# KillSwitch.net
KiCad netlist of a schematic drawn in Altium Designer
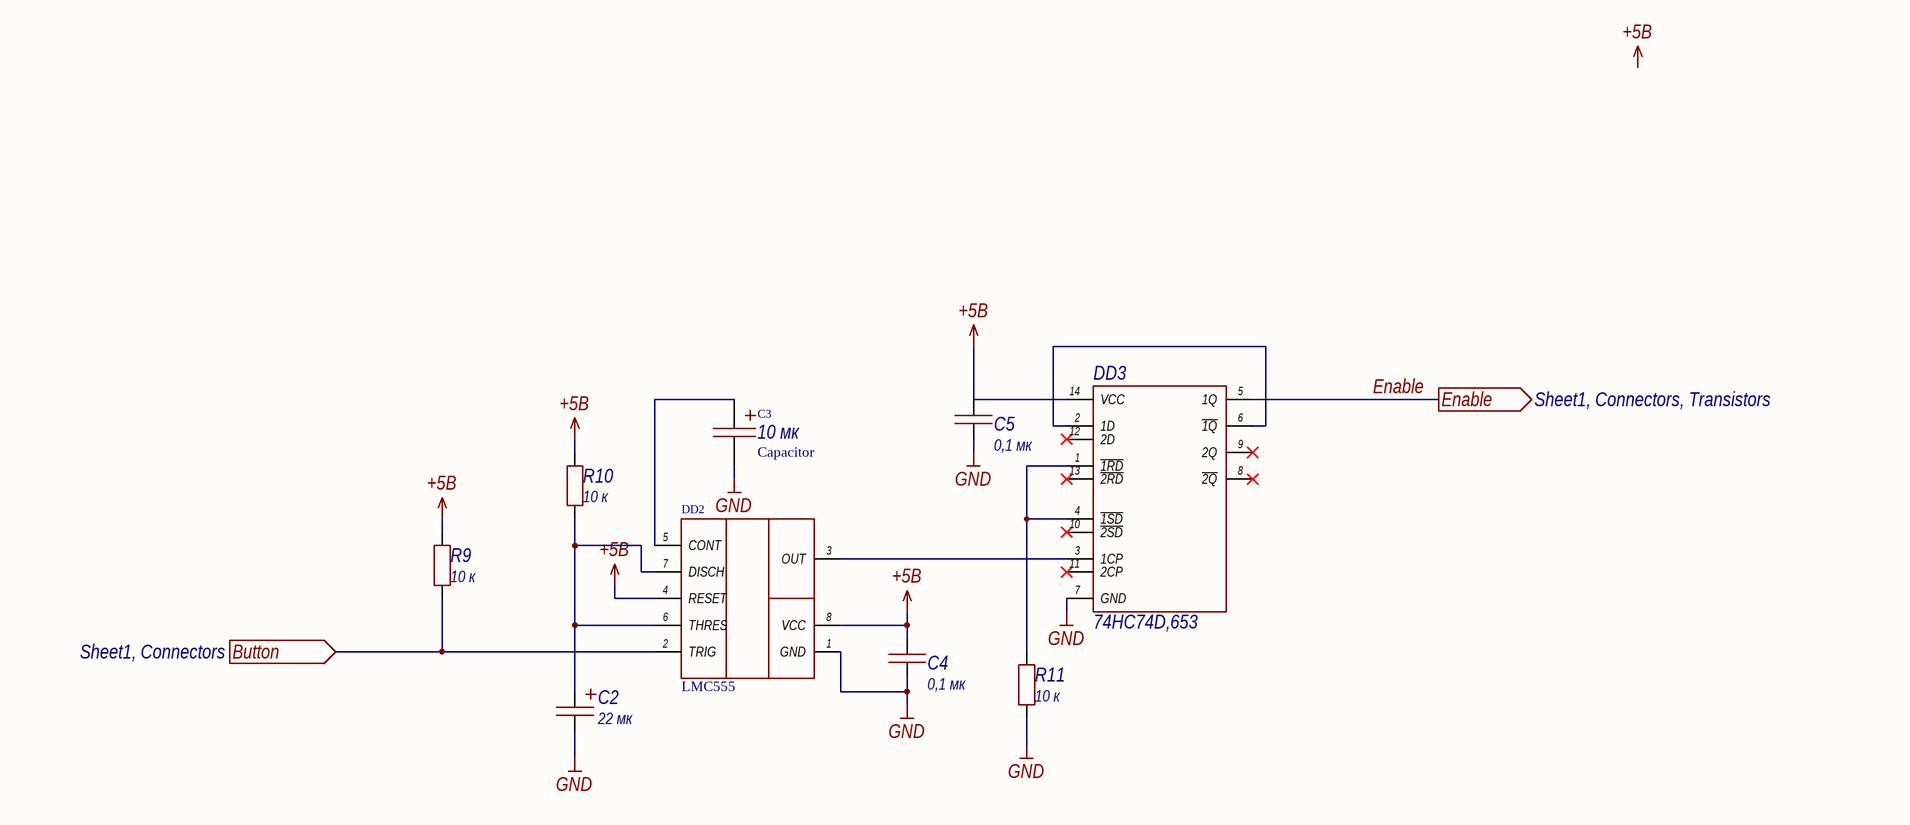
[diagram p0: KillSwitch.SchDoc]

(export (version "E")
  (design (tool "Eeschema 10.0.6"))
  (components
    (comp (ref "C2")
      (value "22 мк")
      (footprint "TC_A")
      (description "Танталовый конденсатор")
      (fields (field (name "PART NUMBER") "Capacitor_22u_10_50V_TC_A") (field (name "TOLERANCE") "0,1"))
      (libsource (lib "Hydrolib") (part "Capacitor_polar"))
    )
    (comp (ref "C3")
      (value "Capacitor")
      (footprint "TC_A")
      (description "Танталовый конденсатор")
      (fields
        (field (name "ALTIUM_VALUE") "10 мк")
        (field (name "PART NUMBER") "Capacitor_10u_10_50V_TC_A")
        (field (name "TOLERANCE") "0,1")
      )
      (libsource (lib "") (part "Capacitor_polar_1"))
    )
    (comp (ref "C4")
      (value "0,1 мк")
      (footprint "0603C")
      (description "Конденсатор")
      (fields (field (name "PART NUMBER") "Capacitor_0,1u_10_50V_X7R_0603C") (field (name "TOLERANCE") "0,1"))
      (libsource (lib "Hydrolib") (part "Capacitor"))
    )
    (comp (ref "C5")
      (value "0,1 мк")
      (footprint "0603C")
      (description "Конденсатор")
      (fields (field (name "PART NUMBER") "Capacitor_0,1u_10_50V_X7R_0603C") (field (name "TOLERANCE") "0,1"))
      (libsource (lib "Hydrolib") (part "Capacitor"))
    )
    (comp (ref "DD2")
      (value "LMC555")
      (footprint "SOIC-8")
      (description "Таймер интегральный прецизионный КМОП")
      (libsource (lib "Hydrolib") (part "NE555"))
    )
    (comp (ref "DD3")
      (value "74HC74D,653")
      (footprint "SOIC-14")
      (description "Два триггера D-типа")
      (fields (field (name "MF") "Nexperia USA"))
      (libsource (lib "Hydrolib") (part "74HC74D,653"))
    )
    (comp (ref "R9")
      (value "10 к")
      (footprint "0603R")
      (description "Резистор номиналом 10 кОм и точностью 1%")
      (fields (field (name "PART NUMBER") "Resistor_10k_1_0603") (field (name "TOLERANCE") "1%"))
      (libsource (lib "Hydrolib") (part "Resistor"))
    )
    (comp (ref "R10")
      (value "10 к")
      (footprint "0603R")
      (description "Резистор номиналом 10 кОм и точностью 1%")
      (fields (field (name "PART NUMBER") "Resistor_10k_1_0603") (field (name "TOLERANCE") "1%"))
      (libsource (lib "Hydrolib") (part "Resistor"))
    )
    (comp (ref "R11")
      (value "10 к")
      (footprint "0603R")
      (description "Резистор номиналом 10 кОм и точностью 1%")
      (fields (field (name "PART NUMBER") "Resistor_10k_1_0603") (field (name "TOLERANCE") "1%"))
      (libsource (lib "Hydrolib") (part "Resistor"))
    )
  )
  (nets
    (net (code "1") (name "+5В") (class "Default")
      (node (ref "C4") (pin "2") (pinfunction "2_2") (pintype "passive"))
      (node (ref "C5") (pin "1") (pinfunction "1_1") (pintype "passive"))
      (node (ref "DD2") (pin "4") (pinfunction "RESET_4") (pintype "passive"))
      (node (ref "DD2") (pin "8") (pinfunction "VCC_8") (pintype "passive"))
      (node (ref "DD3") (pin "14") (pinfunction "VCC_14") (pintype "passive"))
      (node (ref "R10") (pin "2") (pinfunction "2_2") (pintype "passive"))
      (node (ref "R9") (pin "2") (pinfunction "2_2") (pintype "passive"))
    )
    (net (code "2") (name "/Button") (class "Default")
      (node (ref "DD2") (pin "2") (pinfunction "TRIG_2") (pintype "passive"))
      (node (ref "R9") (pin "1") (pinfunction "1_1") (pintype "passive"))
    )
    (net (code "3") (name "/Enable") (class "Default")
      (node (ref "DD3") (pin "5") (pinfunction "1Q_5") (pintype "passive"))
    )
    (net (code "4") (name "GND") (class "Default")
      (node (ref "C2") (pin "2") (pinfunction "2_2") (pintype "passive"))
      (node (ref "C3") (pin "2") (pinfunction "2_2") (pintype "passive"))
      (node (ref "C4") (pin "1") (pinfunction "1_1") (pintype "passive"))
      (node (ref "C5") (pin "2") (pinfunction "2_2") (pintype "passive"))
      (node (ref "DD2") (pin "1") (pinfunction "GND_1") (pintype "passive"))
      (node (ref "DD3") (pin "7") (pinfunction "GND_7") (pintype "passive"))
      (node (ref "R11") (pin "1") (pinfunction "1_1") (pintype "passive"))
    )
    (net (code "5") (name "Net-(DD2-CONT)") (class "Default")
      (node (ref "C3") (pin "1") (pinfunction "1_1") (pintype "passive"))
      (node (ref "DD2") (pin "5") (pinfunction "CONT_5") (pintype "passive"))
    )
    (net (code "6") (name "Net-(DD2-DISCH)") (class "Default")
      (node (ref "C2") (pin "1") (pinfunction "1_1") (pintype "passive"))
      (node (ref "DD2") (pin "6") (pinfunction "THRES_6") (pintype "passive"))
      (node (ref "DD2") (pin "7") (pinfunction "DISCH_7") (pintype "passive"))
      (node (ref "R10") (pin "1") (pinfunction "1_1") (pintype "passive"))
    )
    (net (code "7") (name "Net-(DD2-OUT)") (class "Default")
      (node (ref "DD2") (pin "3") (pinfunction "OUT_3") (pintype "passive"))
      (node (ref "DD3") (pin "3") (pinfunction "1CP_3") (pintype "passive"))
    )
    (net (code "8") (name "Net-(DD3-1D)") (class "Default")
      (node (ref "DD3") (pin "2") (pinfunction "1D_2") (pintype "passive"))
      (node (ref "DD3") (pin "6") (pinfunction "~{1Q}_6") (pintype "passive"))
    )
    (net (code "9") (name "Net-(DD3-~{1RD})") (class "Default")
      (node (ref "DD3") (pin "1") (pinfunction "~{1RD}_1") (pintype "passive"))
      (node (ref "DD3") (pin "4") (pinfunction "~{1SD}_4") (pintype "passive"))
      (node (ref "R11") (pin "2") (pinfunction "2_2") (pintype "passive"))
    )
    (net (code "10") (name "unconnected-(DD3-2CP-Pad11)") (class "Default")
      (node (ref "DD3") (pin "11") (pinfunction "2CP_11") (pintype "passive+no_connect"))
    )
    (net (code "11") (name "unconnected-(DD3-2D-Pad12)") (class "Default")
      (node (ref "DD3") (pin "12") (pinfunction "2D_12") (pintype "passive+no_connect"))
    )
    (net (code "12") (name "unconnected-(DD3-2Q-Pad9)") (class "Default")
      (node (ref "DD3") (pin "9") (pinfunction "2Q_9") (pintype "passive+no_connect"))
    )
    (net (code "13") (name "unconnected-(DD3-~{2Q}-Pad8)") (class "Default")
      (node (ref "DD3") (pin "8") (pinfunction "~{2Q}_8") (pintype "passive+no_connect"))
    )
    (net (code "14") (name "unconnected-(DD3-~{2RD}-Pad13)") (class "Default")
      (node (ref "DD3") (pin "13") (pinfunction "~{2RD}_13") (pintype "passive+no_connect"))
    )
    (net (code "15") (name "unconnected-(DD3-~{2SD}-Pad10)") (class "Default")
      (node (ref "DD3") (pin "10") (pinfunction "~{2SD}_10") (pintype "passive+no_connect"))
    )
  )
)
